# DanSquidControlAdapterBoard.net
KiCad netlist of a schematic drawn in Altium Designer
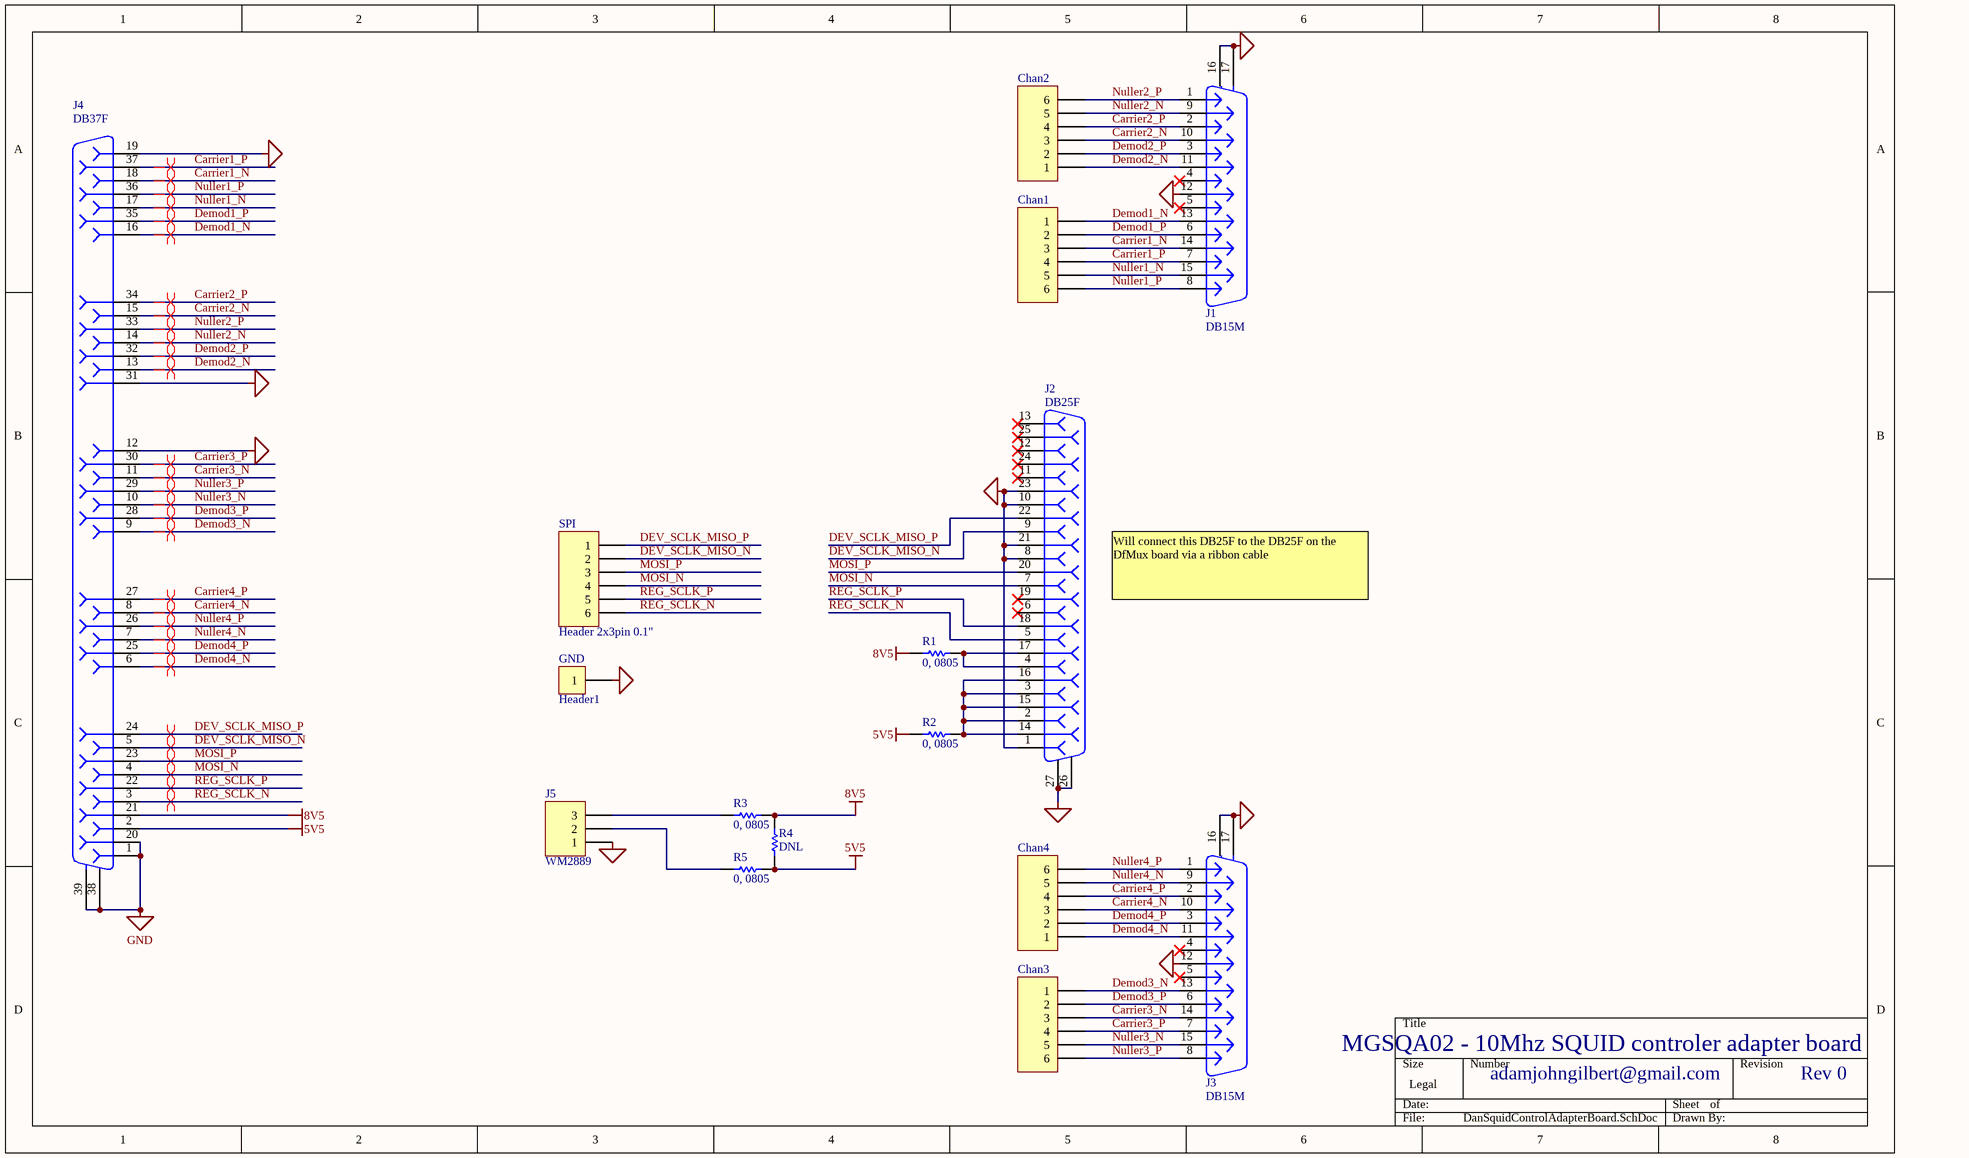
[diagram p0: DanSquidControlAdapterBoard.SchDoc]

(export (version "E")
  (design (tool "Eeschema 10.0.6"))
  (components
    (comp (ref "Chan1")
      (value "Header 2x3pin 0.1\"")
      (footprint "HDR2X3")
      (libsource (lib "") (part "Header2x3_1"))
    )
    (comp (ref "Chan2")
      (value "Header 2x3pin 0.1\"")
      (footprint "HDR2X3")
      (libsource (lib "DanSquidAdapterParts") (part "Header2x3"))
    )
    (comp (ref "Chan3")
      (value "Header 2x3pin 0.1\"")
      (footprint "HDR2X3")
      (libsource (lib "") (part "Header2x3_1"))
    )
    (comp (ref "Chan4")
      (value "Header 2x3pin 0.1\"")
      (footprint "HDR2X3")
      (libsource (lib "DanSquidAdapterParts") (part "Header2x3"))
    )
    (comp (ref "GND")
      (value "Header1")
      (footprint "HDR1")
      (description "TestPoint1")
      (libsource (lib "DanSquidAdapterParts") (part "Header1"))
    )
    (comp (ref "J1")
      (value "DB15M")
      (footprint "DSUB15-M")
      (libsource (lib "DanSquidAdapterParts") (part "DB15M"))
    )
    (comp (ref "J2")
      (value "DB25F")
      (footprint "DSUB25-F - Vertical")
      (libsource (lib "DanSquidAdapterParts") (part "DB25F"))
    )
    (comp (ref "J3")
      (value "DB15M")
      (footprint "DSUB15-M")
      (libsource (lib "DanSquidAdapterParts") (part "DB15M"))
    )
    (comp (ref "J4")
      (value "DB37F")
      (footprint "DSUB37-F")
      (fields (field (name "MANUFACTURER") "Generic") (field (name "MANUFACTURER PART NUMBER") "DB37F"))
      (libsource (lib "DanSquidAdapterParts") (part "DB37F"))
    )
    (comp (ref "J5")
      (value "WM2889")
      (footprint "HDR1X3_MolexVertical")
      (description "Header, 0.1\"  3-Pin straight (Any equivalent - may need to be value added)")
      (fields (field (name "MANUFACTURER") "Digikey"))
      (libsource (lib "DanSquidAdapterParts") (part "Header 3"))
    )
    (comp (ref "R1")
      (value "0, 0805")
      (footprint "0805")
      (description "RES 0.0 OHM 1/8W 0805 SMD")
      (fields (field (name "MANUFACTURER") "e.g Vishay/Dale"))
      (libsource (lib "DanSquidAdapterParts") (part "RES 0805"))
    )
    (comp (ref "R2")
      (value "0, 0805")
      (footprint "0805")
      (description "RES 0.0 OHM 1/8W 0805 SMD")
      (fields (field (name "MANUFACTURER") "e.g Vishay/Dale"))
      (libsource (lib "DanSquidAdapterParts") (part "RES 0805"))
    )
    (comp (ref "R3")
      (value "0, 0805")
      (footprint "0805")
      (description "RES 0.0 OHM 1/8W 0805 SMD")
      (fields (field (name "MANUFACTURER") "e.g Vishay/Dale"))
      (libsource (lib "DanSquidAdapterParts") (part "RES 0805"))
    )
    (comp (ref "R4")
      (value "DNL")
      (footprint "0805")
      (description "RES 0.0 OHM 1/8W 0805 SMD")
      (fields (field (name "MANUFACTURER") "e.g Vishay/Dale"))
      (libsource (lib "DanSquidAdapterParts") (part "RES 0805"))
    )
    (comp (ref "R5")
      (value "0, 0805")
      (footprint "0805")
      (description "RES 0.0 OHM 1/8W 0805 SMD")
      (fields (field (name "MANUFACTURER") "e.g Vishay/Dale"))
      (libsource (lib "DanSquidAdapterParts") (part "RES 0805"))
    )
    (comp (ref "SPI")
      (value "Header 2x3pin 0.1\"")
      (footprint "HDR2X3")
      (libsource (lib "") (part "Header2x3_1"))
    )
  )
  (nets
    (net (code "1") (name "/Carrier1_N") (class "Default")
      (node (ref "Chan1") (pin "3") (pinfunction "3_3") (pintype "passive"))
      (node (ref "J1") (pin "14") (pinfunction "14_14") (pintype "passive"))
      (node (ref "J4") (pin "18") (pinfunction "18_18") (pintype "passive"))
    )
    (net (code "2") (name "/Carrier1_P") (class "Default")
      (node (ref "Chan1") (pin "4") (pinfunction "4_4") (pintype "passive"))
      (node (ref "J1") (pin "7") (pinfunction "7_7") (pintype "passive"))
      (node (ref "J4") (pin "37") (pinfunction "37_37") (pintype "passive"))
    )
    (net (code "3") (name "/Carrier2_N") (class "Default")
      (node (ref "Chan2") (pin "3") (pinfunction "3_3") (pintype "passive"))
      (node (ref "J1") (pin "10") (pinfunction "10_10") (pintype "passive"))
      (node (ref "J4") (pin "15") (pinfunction "15_15") (pintype "passive"))
    )
    (net (code "4") (name "/Carrier2_P") (class "Default")
      (node (ref "Chan2") (pin "4") (pinfunction "4_4") (pintype "passive"))
      (node (ref "J1") (pin "2") (pinfunction "2_2") (pintype "passive"))
      (node (ref "J4") (pin "34") (pinfunction "34_34") (pintype "passive"))
    )
    (net (code "5") (name "/Carrier3_N") (class "Default")
      (node (ref "Chan3") (pin "3") (pinfunction "3_3") (pintype "passive"))
      (node (ref "J3") (pin "14") (pinfunction "14_14") (pintype "passive"))
      (node (ref "J4") (pin "11") (pinfunction "11_11") (pintype "passive"))
    )
    (net (code "6") (name "/Carrier3_P") (class "Default")
      (node (ref "Chan3") (pin "4") (pinfunction "4_4") (pintype "passive"))
      (node (ref "J3") (pin "7") (pinfunction "7_7") (pintype "passive"))
      (node (ref "J4") (pin "30") (pinfunction "30_30") (pintype "passive"))
    )
    (net (code "7") (name "/Carrier4_N") (class "Default")
      (node (ref "Chan4") (pin "3") (pinfunction "3_3") (pintype "passive"))
      (node (ref "J3") (pin "10") (pinfunction "10_10") (pintype "passive"))
      (node (ref "J4") (pin "8") (pinfunction "8_8") (pintype "passive"))
    )
    (net (code "8") (name "/Carrier4_P") (class "Default")
      (node (ref "Chan4") (pin "4") (pinfunction "4_4") (pintype "passive"))
      (node (ref "J3") (pin "2") (pinfunction "2_2") (pintype "passive"))
      (node (ref "J4") (pin "27") (pinfunction "27_27") (pintype "passive"))
    )
    (net (code "9") (name "/DEV_SCLK_MISO_N") (class "Default")
      (node (ref "J2") (pin "9") (pinfunction "9_9") (pintype "passive"))
      (node (ref "J4") (pin "5") (pinfunction "5_5") (pintype "passive"))
      (node (ref "SPI") (pin "2") (pinfunction "2_2") (pintype "passive"))
    )
    (net (code "10") (name "/DEV_SCLK_MISO_P") (class "Default")
      (node (ref "J2") (pin "22") (pinfunction "22_22") (pintype "passive"))
      (node (ref "J4") (pin "24") (pinfunction "24_24") (pintype "passive"))
      (node (ref "SPI") (pin "1") (pinfunction "1_1") (pintype "passive"))
    )
    (net (code "11") (name "/Demod1_N") (class "Default")
      (node (ref "Chan1") (pin "1") (pinfunction "1_1") (pintype "passive"))
      (node (ref "J1") (pin "13") (pinfunction "13_13") (pintype "passive"))
      (node (ref "J4") (pin "16") (pinfunction "16_16") (pintype "passive"))
    )
    (net (code "12") (name "/Demod1_P") (class "Default")
      (node (ref "Chan1") (pin "2") (pinfunction "2_2") (pintype "passive"))
      (node (ref "J1") (pin "6") (pinfunction "6_6") (pintype "passive"))
      (node (ref "J4") (pin "35") (pinfunction "35_35") (pintype "passive"))
    )
    (net (code "13") (name "/Demod2_N") (class "Default")
      (node (ref "Chan2") (pin "1") (pinfunction "1_1") (pintype "passive"))
      (node (ref "J1") (pin "11") (pinfunction "11_11") (pintype "passive"))
      (node (ref "J4") (pin "13") (pinfunction "13_13") (pintype "passive"))
    )
    (net (code "14") (name "/Demod2_P") (class "Default")
      (node (ref "Chan2") (pin "2") (pinfunction "2_2") (pintype "passive"))
      (node (ref "J1") (pin "3") (pinfunction "3_3") (pintype "passive"))
      (node (ref "J4") (pin "32") (pinfunction "32_32") (pintype "passive"))
    )
    (net (code "15") (name "/Demod3_N") (class "Default")
      (node (ref "Chan3") (pin "1") (pinfunction "1_1") (pintype "passive"))
      (node (ref "J3") (pin "13") (pinfunction "13_13") (pintype "passive"))
      (node (ref "J4") (pin "9") (pinfunction "9_9") (pintype "passive"))
    )
    (net (code "16") (name "/Demod3_P") (class "Default")
      (node (ref "Chan3") (pin "2") (pinfunction "2_2") (pintype "passive"))
      (node (ref "J3") (pin "6") (pinfunction "6_6") (pintype "passive"))
      (node (ref "J4") (pin "28") (pinfunction "28_28") (pintype "passive"))
    )
    (net (code "17") (name "/Demod4_N") (class "Default")
      (node (ref "Chan4") (pin "1") (pinfunction "1_1") (pintype "passive"))
      (node (ref "J3") (pin "11") (pinfunction "11_11") (pintype "passive"))
      (node (ref "J4") (pin "6") (pinfunction "6_6") (pintype "passive"))
    )
    (net (code "18") (name "/Demod4_P") (class "Default")
      (node (ref "Chan4") (pin "2") (pinfunction "2_2") (pintype "passive"))
      (node (ref "J3") (pin "3") (pinfunction "3_3") (pintype "passive"))
      (node (ref "J4") (pin "25") (pinfunction "25_25") (pintype "passive"))
    )
    (net (code "19") (name "/MOSI_N") (class "Default")
      (node (ref "J2") (pin "7") (pinfunction "7_7") (pintype "passive"))
      (node (ref "J4") (pin "4") (pinfunction "4_4") (pintype "passive"))
      (node (ref "SPI") (pin "4") (pinfunction "4_4") (pintype "passive"))
    )
    (net (code "20") (name "/MOSI_P") (class "Default")
      (node (ref "J2") (pin "20") (pinfunction "20_20") (pintype "passive"))
      (node (ref "J4") (pin "23") (pinfunction "23_23") (pintype "passive"))
      (node (ref "SPI") (pin "3") (pinfunction "3_3") (pintype "passive"))
    )
    (net (code "21") (name "/Nuller1_N") (class "Default")
      (node (ref "Chan1") (pin "5") (pinfunction "5_5") (pintype "passive"))
      (node (ref "J1") (pin "15") (pinfunction "15_15") (pintype "passive"))
      (node (ref "J4") (pin "17") (pinfunction "17_17") (pintype "passive"))
    )
    (net (code "22") (name "/Nuller1_P") (class "Default")
      (node (ref "Chan1") (pin "6") (pinfunction "6_6") (pintype "passive"))
      (node (ref "J1") (pin "8") (pinfunction "8_8") (pintype "passive"))
      (node (ref "J4") (pin "36") (pinfunction "36_36") (pintype "passive"))
    )
    (net (code "23") (name "/Nuller2_N") (class "Default")
      (node (ref "Chan2") (pin "5") (pinfunction "5_5") (pintype "passive"))
      (node (ref "J1") (pin "9") (pinfunction "9_9") (pintype "passive"))
      (node (ref "J4") (pin "14") (pinfunction "14_14") (pintype "passive"))
    )
    (net (code "24") (name "/Nuller2_P") (class "Default")
      (node (ref "Chan2") (pin "6") (pinfunction "6_6") (pintype "passive"))
      (node (ref "J1") (pin "1") (pinfunction "1_1") (pintype "passive"))
      (node (ref "J4") (pin "33") (pinfunction "33_33") (pintype "passive"))
    )
    (net (code "25") (name "/Nuller3_N") (class "Default")
      (node (ref "Chan3") (pin "5") (pinfunction "5_5") (pintype "passive"))
      (node (ref "J3") (pin "15") (pinfunction "15_15") (pintype "passive"))
      (node (ref "J4") (pin "10") (pinfunction "10_10") (pintype "passive"))
    )
    (net (code "26") (name "/Nuller3_P") (class "Default")
      (node (ref "Chan3") (pin "6") (pinfunction "6_6") (pintype "passive"))
      (node (ref "J3") (pin "8") (pinfunction "8_8") (pintype "passive"))
      (node (ref "J4") (pin "29") (pinfunction "29_29") (pintype "passive"))
    )
    (net (code "27") (name "/Nuller4_N") (class "Default")
      (node (ref "Chan4") (pin "5") (pinfunction "5_5") (pintype "passive"))
      (node (ref "J3") (pin "9") (pinfunction "9_9") (pintype "passive"))
      (node (ref "J4") (pin "7") (pinfunction "7_7") (pintype "passive"))
    )
    (net (code "28") (name "/Nuller4_P") (class "Default")
      (node (ref "Chan4") (pin "6") (pinfunction "6_6") (pintype "passive"))
      (node (ref "J3") (pin "1") (pinfunction "1_1") (pintype "passive"))
      (node (ref "J4") (pin "26") (pinfunction "26_26") (pintype "passive"))
    )
    (net (code "29") (name "/REG_SCLK_N") (class "Default")
      (node (ref "J2") (pin "5") (pinfunction "5_5") (pintype "passive"))
      (node (ref "J4") (pin "3") (pinfunction "3_3") (pintype "passive"))
      (node (ref "SPI") (pin "6") (pinfunction "6_6") (pintype "passive"))
    )
    (net (code "30") (name "/REG_SCLK_P") (class "Default")
      (node (ref "J2") (pin "18") (pinfunction "18_18") (pintype "passive"))
      (node (ref "J4") (pin "22") (pinfunction "22_22") (pintype "passive"))
      (node (ref "SPI") (pin "5") (pinfunction "5_5") (pintype "passive"))
    )
    (net (code "31") (name "5V5") (class "Default")
      (node (ref "J4") (pin "2") (pinfunction "2_2") (pintype "passive"))
      (node (ref "R2") (pin "1") (pinfunction "1_1") (pintype "passive"))
      (node (ref "R4") (pin "1") (pinfunction "1_1") (pintype "passive"))
      (node (ref "R5") (pin "2") (pinfunction "2_2") (pintype "passive"))
    )
    (net (code "32") (name "8V5") (class "Default")
      (node (ref "J4") (pin "21") (pinfunction "21_21") (pintype "passive"))
      (node (ref "R1") (pin "1") (pinfunction "1_1") (pintype "passive"))
      (node (ref "R3") (pin "2") (pinfunction "2_2") (pintype "passive"))
      (node (ref "R4") (pin "2") (pinfunction "2_2") (pintype "passive"))
    )
    (net (code "33") (name "GND") (class "Default")
      (node (ref "GND") (pin "1") (pinfunction "1_1") (pintype "passive"))
      (node (ref "J1") (pin "12") (pinfunction "12_12") (pintype "passive"))
      (node (ref "J1") (pin "16") (pinfunction "MH1_16") (pintype "passive"))
      (node (ref "J1") (pin "17") (pinfunction "MH2_17") (pintype "passive"))
      (node (ref "J2") (pin "1") (pinfunction "1_1") (pintype "passive"))
      (node (ref "J2") (pin "10") (pinfunction "10_10") (pintype "passive"))
      (node (ref "J2") (pin "21") (pinfunction "21_21") (pintype "passive"))
      (node (ref "J2") (pin "23") (pinfunction "23_23") (pintype "passive"))
      (node (ref "J2") (pin "26") (pinfunction "MH1_26") (pintype "passive"))
      (node (ref "J2") (pin "27") (pinfunction "MH2_27") (pintype "passive"))
      (node (ref "J2") (pin "8") (pinfunction "8_8") (pintype "passive"))
      (node (ref "J3") (pin "12") (pinfunction "12_12") (pintype "passive"))
      (node (ref "J3") (pin "16") (pinfunction "MH1_16") (pintype "passive"))
      (node (ref "J3") (pin "17") (pinfunction "MH2_17") (pintype "passive"))
      (node (ref "J4") (pin "1") (pinfunction "1_1") (pintype "passive"))
      (node (ref "J4") (pin "12") (pinfunction "12_12") (pintype "passive"))
      (node (ref "J4") (pin "19") (pinfunction "19_19") (pintype "passive"))
      (node (ref "J4") (pin "20") (pinfunction "20_20") (pintype "passive"))
      (node (ref "J4") (pin "31") (pinfunction "31_31") (pintype "passive"))
      (node (ref "J4") (pin "38") (pinfunction "MH1_38") (pintype "passive"))
      (node (ref "J4") (pin "39") (pinfunction "MH2_39") (pintype "passive"))
      (node (ref "J5") (pin "1") (pinfunction "1_1") (pintype "passive"))
    )
    (net (code "34") (name "Net-(J2-Pad14)") (class "Default")
      (node (ref "J2") (pin "14") (pinfunction "14_14") (pintype "passive"))
      (node (ref "J2") (pin "15") (pinfunction "15_15") (pintype "passive"))
      (node (ref "J2") (pin "16") (pinfunction "16_16") (pintype "passive"))
      (node (ref "J2") (pin "2") (pinfunction "2_2") (pintype "passive"))
      (node (ref "J2") (pin "3") (pinfunction "3_3") (pintype "passive"))
      (node (ref "R2") (pin "2") (pinfunction "2_2") (pintype "passive"))
    )
    (net (code "35") (name "Net-(J2-Pad17)") (class "Default")
      (node (ref "J2") (pin "17") (pinfunction "17_17") (pintype "passive"))
      (node (ref "J2") (pin "4") (pinfunction "4_4") (pintype "passive"))
      (node (ref "R1") (pin "2") (pinfunction "2_2") (pintype "passive"))
    )
    (net (code "36") (name "Net-(J5-Pad2)") (class "Default")
      (node (ref "J5") (pin "2") (pinfunction "2_2") (pintype "passive"))
      (node (ref "R5") (pin "1") (pinfunction "1_1") (pintype "passive"))
    )
    (net (code "37") (name "Net-(J5-Pad3)") (class "Default")
      (node (ref "J5") (pin "3") (pinfunction "3_3") (pintype "passive"))
      (node (ref "R3") (pin "1") (pinfunction "1_1") (pintype "passive"))
    )
    (net (code "38") (name "unconnected-(J1-Pad4)") (class "Default")
      (node (ref "J1") (pin "4") (pinfunction "4_4") (pintype "passive+no_connect"))
    )
    (net (code "39") (name "unconnected-(J1-Pad5)") (class "Default")
      (node (ref "J1") (pin "5") (pinfunction "5_5") (pintype "passive+no_connect"))
    )
    (net (code "40") (name "unconnected-(J2-Pad6)") (class "Default")
      (node (ref "J2") (pin "6") (pinfunction "6_6") (pintype "passive+no_connect"))
    )
    (net (code "41") (name "unconnected-(J2-Pad11)") (class "Default")
      (node (ref "J2") (pin "11") (pinfunction "11_11") (pintype "passive+no_connect"))
    )
    (net (code "42") (name "unconnected-(J2-Pad12)") (class "Default")
      (node (ref "J2") (pin "12") (pinfunction "12_12") (pintype "passive+no_connect"))
    )
    (net (code "43") (name "unconnected-(J2-Pad13)") (class "Default")
      (node (ref "J2") (pin "13") (pinfunction "13_13") (pintype "passive+no_connect"))
    )
    (net (code "44") (name "unconnected-(J2-Pad19)") (class "Default")
      (node (ref "J2") (pin "19") (pinfunction "19_19") (pintype "passive+no_connect"))
    )
    (net (code "45") (name "unconnected-(J2-Pad24)") (class "Default")
      (node (ref "J2") (pin "24") (pinfunction "24_24") (pintype "passive+no_connect"))
    )
    (net (code "46") (name "unconnected-(J2-Pad25)") (class "Default")
      (node (ref "J2") (pin "25") (pinfunction "25_25") (pintype "passive+no_connect"))
    )
    (net (code "47") (name "unconnected-(J3-Pad4)") (class "Default")
      (node (ref "J3") (pin "4") (pinfunction "4_4") (pintype "passive+no_connect"))
    )
    (net (code "48") (name "unconnected-(J3-Pad5)") (class "Default")
      (node (ref "J3") (pin "5") (pinfunction "5_5") (pintype "passive+no_connect"))
    )
  )
)
